# Custom_Board_1_Final.net
KiCad netlist of a schematic drawn in EAGLE
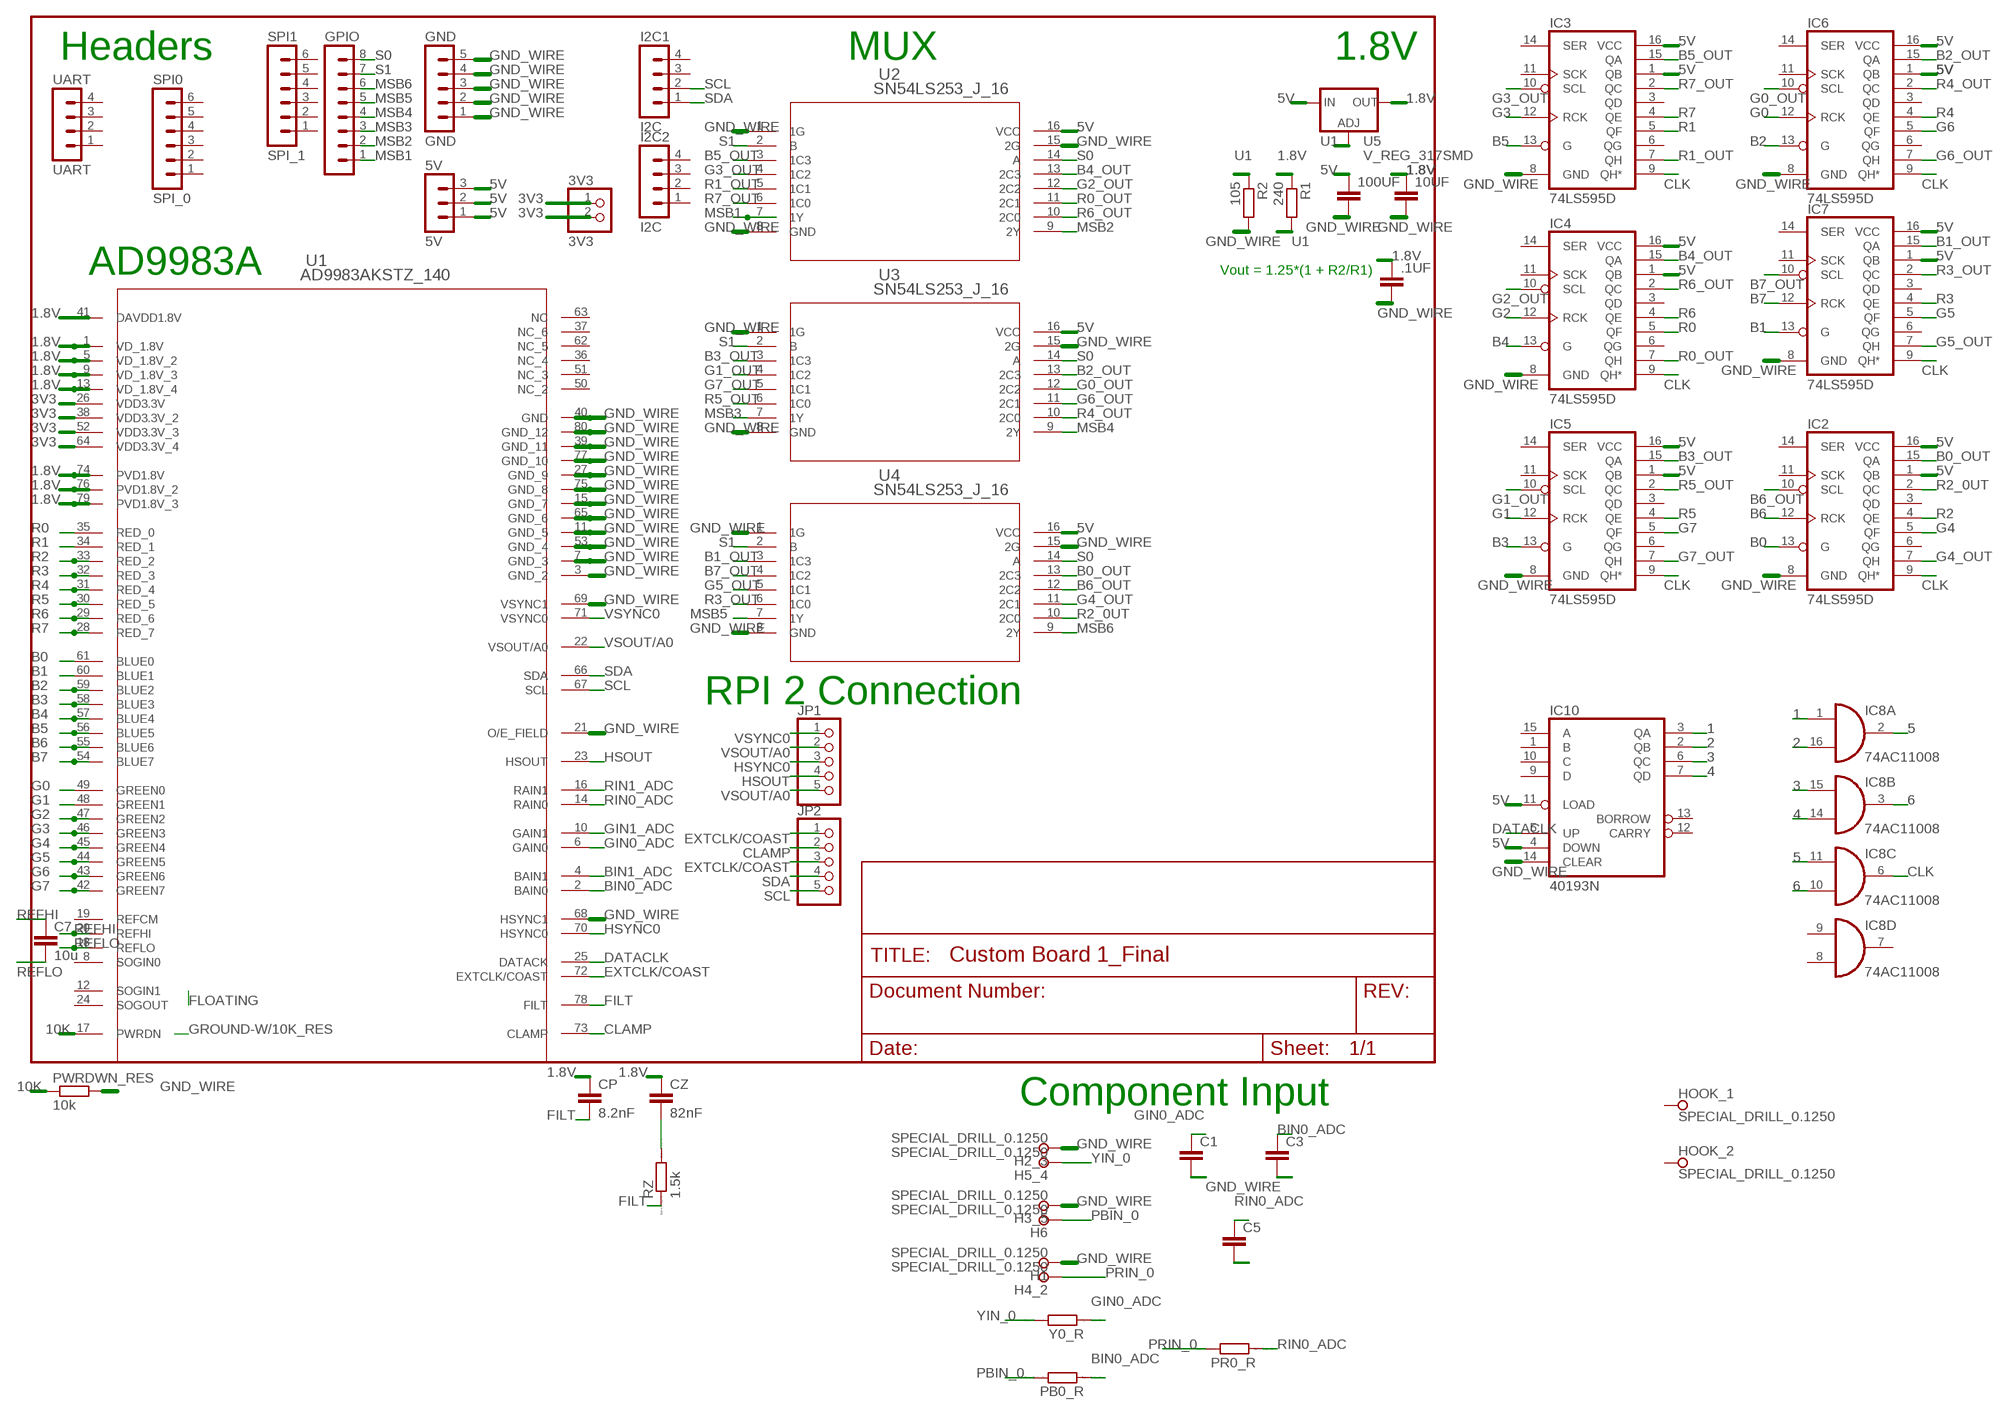
[diagram p0: schematic, sheet 1]

(export (version "E")
  (design (tool "Eeschema 10.0.6"))
  (components
    (comp (ref ".1UF")
      (value "C2.5/5")
      (footprint "eagle-import:C2.5-5")
      (libsource (lib "eagle-import") (part "C2.5/5"))
    )
    (comp (ref "3V3")
      (value "3V3")
      (footprint "eagle-import:1X02")
      (libsource (lib "eagle-import") (part "PINHD-1X2"))
    )
    (comp (ref "5V")
      (value "5V")
      (footprint "eagle-import:MA03-1")
      (libsource (lib "eagle-import") (part "MA03-1"))
    )
    (comp (ref "10UF")
      (value "C2.5/5")
      (footprint "eagle-import:C2.5-5")
      (libsource (lib "eagle-import") (part "C2.5/5"))
    )
    (comp (ref "100UF")
      (value "C2.5/5")
      (footprint "eagle-import:C2.5-5")
      (libsource (lib "eagle-import") (part "C2.5/5"))
    )
    (comp (ref "C1")
      (value "C2.5/5")
      (footprint "eagle-import:C2.5-5")
      (libsource (lib "eagle-import") (part "C2.5/5"))
    )
    (comp (ref "C3")
      (value "C2.5/5")
      (footprint "eagle-import:C2.5-5")
      (libsource (lib "eagle-import") (part "C2.5/5"))
    )
    (comp (ref "C5")
      (value "C2.5/5")
      (footprint "eagle-import:C2.5-5")
      (libsource (lib "eagle-import") (part "C2.5/5"))
    )
    (comp (ref "C7")
      (value "10u")
      (footprint "eagle-import:C2.5-5")
      (libsource (lib "eagle-import") (part "C2.5/5"))
    )
    (comp (ref "CP")
      (value "8.2nF")
      (footprint "eagle-import:C2.5-5")
      (libsource (lib "eagle-import") (part "C2.5/5"))
    )
    (comp (ref "CZ")
      (value "82nF")
      (footprint "eagle-import:C2.5-5")
      (libsource (lib "eagle-import") (part "C2.5/5"))
    )
    (comp (ref "GND")
      (value "GND")
      (footprint "eagle-import:MA05-1")
      (libsource (lib "eagle-import") (part "MA05-1"))
    )
    (comp (ref "GPIO")
      (value "MA08-1")
      (footprint "eagle-import:MA08-1")
      (libsource (lib "eagle-import") (part "MA08-1"))
    )
    (comp (ref "H1")
      (value "SPECIAL_DRILL_0.1250")
      (footprint "eagle-import:PAD_0.1250")
      (libsource (lib "eagle-import") (part "SPECIAL_DRILL_0.1250"))
    )
    (comp (ref "H2_3")
      (value "SPECIAL_DRILL_0.1250")
      (footprint "eagle-import:PAD_0.1250")
      (libsource (lib "eagle-import") (part "SPECIAL_DRILL_0.1250"))
    )
    (comp (ref "H3_5")
      (value "SPECIAL_DRILL_0.1250")
      (footprint "eagle-import:PAD_0.1250")
      (libsource (lib "eagle-import") (part "SPECIAL_DRILL_0.1250"))
    )
    (comp (ref "H4_2")
      (value "SPECIAL_DRILL_0.1250")
      (footprint "eagle-import:PAD_0.1250")
      (libsource (lib "eagle-import") (part "SPECIAL_DRILL_0.1250"))
    )
    (comp (ref "H5_4")
      (value "SPECIAL_DRILL_0.1250")
      (footprint "eagle-import:PAD_0.1250")
      (libsource (lib "eagle-import") (part "SPECIAL_DRILL_0.1250"))
    )
    (comp (ref "H6")
      (value "SPECIAL_DRILL_0.1250")
      (footprint "eagle-import:PAD_0.1250")
      (libsource (lib "eagle-import") (part "SPECIAL_DRILL_0.1250"))
    )
    (comp (ref "HOOK_1")
      (value "SPECIAL_DRILL_0.1250")
      (footprint "eagle-import:PAD_0.1250")
      (libsource (lib "eagle-import") (part "SPECIAL_DRILL_0.1250"))
    )
    (comp (ref "HOOK_2")
      (value "SPECIAL_DRILL_0.1250")
      (footprint "eagle-import:PAD_0.1250")
      (libsource (lib "eagle-import") (part "SPECIAL_DRILL_0.1250"))
    )
    (comp (ref "I2C1")
      (value "I2C")
      (footprint "eagle-import:MA04-1")
      (libsource (lib "eagle-import") (part "MA04-1"))
    )
    (comp (ref "I2C2")
      (value "I2C")
      (footprint "eagle-import:MA04-1")
      (libsource (lib "eagle-import") (part "MA04-1"))
    )
    (comp (ref "IC2")
      (value "74LS595D")
      (footprint "eagle-import:SO16")
      (libsource (lib "eagle-import") (part "74595DLS"))
    )
    (comp (ref "IC3")
      (value "74LS595D")
      (footprint "eagle-import:SO16")
      (libsource (lib "eagle-import") (part "74595DLS"))
    )
    (comp (ref "IC4")
      (value "74LS595D")
      (footprint "eagle-import:SO16")
      (libsource (lib "eagle-import") (part "74595DLS"))
    )
    (comp (ref "IC5")
      (value "74LS595D")
      (footprint "eagle-import:SO16")
      (libsource (lib "eagle-import") (part "74595DLS"))
    )
    (comp (ref "IC6")
      (value "74LS595D")
      (footprint "eagle-import:SO16")
      (libsource (lib "eagle-import") (part "74595DLS"))
    )
    (comp (ref "IC7")
      (value "74LS595D")
      (footprint "eagle-import:SO16")
      (libsource (lib "eagle-import") (part "74595DLS"))
    )
    (comp (ref "IC8")
      (value "74AC11008")
      (footprint "eagle-import:DIL16")
      (libsource (lib "eagle-import") (part "74AC11008"))
    )
    (comp (ref "IC10")
      (value "40193N")
      (footprint "eagle-import:DIL16")
      (libsource (lib "eagle-import") (part "40193N"))
    )
    (comp (ref "JP1")
      (value "PINHD-1X5")
      (footprint "eagle-import:1X05")
      (libsource (lib "eagle-import") (part "PINHD-1X5"))
    )
    (comp (ref "JP2")
      (value "PINHD-1X5")
      (footprint "eagle-import:1X05")
      (libsource (lib "eagle-import") (part "PINHD-1X5"))
    )
    (comp (ref "PB0_R")
      (value "R0204/7")
      (footprint "eagle-import:0204_7")
      (libsource (lib "eagle-import") (part "R0204/7"))
    )
    (comp (ref "PR0_R")
      (value "R0204/7")
      (footprint "eagle-import:0204_7")
      (libsource (lib "eagle-import") (part "R0204/7"))
    )
    (comp (ref "PWRDWN_RES")
      (value "10k")
      (footprint "eagle-import:0204_7")
      (libsource (lib "eagle-import") (part "R-EU_0204/7"))
    )
    (comp (ref "R1")
      (value "240")
      (footprint "eagle-import:0204_7")
      (libsource (lib "eagle-import") (part "R-EU_0204/7"))
    )
    (comp (ref "R2")
      (value "105")
      (footprint "eagle-import:0204_7")
      (libsource (lib "eagle-import") (part "R-EU_0204/7"))
    )
    (comp (ref "RZ")
      (value "1.5k")
      (footprint "eagle-import:0204_7")
      (libsource (lib "eagle-import") (part "R0204/7"))
    )
    (comp (ref "SPI0")
      (value "SPI_0")
      (footprint "eagle-import:MA06-1")
      (libsource (lib "eagle-import") (part "MA06-1"))
    )
    (comp (ref "SPI1")
      (value "SPI_1")
      (footprint "eagle-import:MA06-1")
      (libsource (lib "eagle-import") (part "MA06-1"))
    )
    (comp (ref "U1")
      (value "AD9983AKSTZ_140")
      (footprint "eagle-import:ST_80_2")
      (libsource (lib "eagle-import") (part "AD9983AKSTZ_140"))
    )
    (comp (ref "U2")
      (value "SN54LS253_J_16")
      (footprint "eagle-import:J16")
      (fields
        (field (name "GENERIC_PART_NUMBER") "SN54LS253")
        (field (name "MANUFACTURER") "Texas Instruments")
      )
      (libsource (lib "eagle-import") (part "SN54LS253_J_16"))
    )
    (comp (ref "U3")
      (value "SN54LS253_J_16")
      (footprint "eagle-import:J16")
      (fields
        (field (name "GENERIC_PART_NUMBER") "SN54LS253")
        (field (name "MANUFACTURER") "Texas Instruments")
      )
      (libsource (lib "eagle-import") (part "SN54LS253_J_16"))
    )
    (comp (ref "U4")
      (value "SN54LS253_J_16")
      (footprint "eagle-import:J16")
      (fields
        (field (name "GENERIC_PART_NUMBER") "SN54LS253")
        (field (name "MANUFACTURER") "Texas Instruments")
      )
      (libsource (lib "eagle-import") (part "SN54LS253_J_16"))
    )
    (comp (ref "U5")
      (value "V_REG_317SMD")
      (footprint "eagle-import:SOT223")
      (libsource (lib "eagle-import") (part "V_REG_317SMD"))
    )
    (comp (ref "UART")
      (value "UART")
      (footprint "eagle-import:MA04-1")
      (libsource (lib "eagle-import") (part "MA04-1"))
    )
    (comp (ref "Y0_R")
      (value "R0204/7")
      (footprint "eagle-import:0204_7")
      (libsource (lib "eagle-import") (part "R0204/7"))
    )
  )
  (nets
    (net (code "1") (name "/1") (class "Default")
      (node (ref "IC10") (pin "3") (pinfunction "QA_3") (pintype "output"))
      (node (ref "IC8") (pin "1") (pinfunction "I0_1") (pintype "input"))
    )
    (net (code "2") (name "/1.8V") (class "Default")
      (node (ref ".1UF") (pin "1") (pinfunction "1_1") (pintype "passive"))
      (node (ref "10UF") (pin "1") (pinfunction "1_1") (pintype "passive"))
      (node (ref "CP") (pin "1") (pinfunction "1_1") (pintype "passive"))
      (node (ref "CZ") (pin "1") (pinfunction "1_1") (pintype "passive"))
      (node (ref "R1") (pin "1") (pinfunction "1_1") (pintype "passive"))
      (node (ref "U1") (pin "1") (pinfunction "VD_1.8V_1") (pintype "passive"))
      (node (ref "U1") (pin "13") (pinfunction "VD_1.8V_4_13") (pintype "passive"))
      (node (ref "U1") (pin "41") (pinfunction "DAVDD1.8V_41") (pintype "passive"))
      (node (ref "U1") (pin "5") (pinfunction "VD_1.8V_2_5") (pintype "passive"))
      (node (ref "U1") (pin "74") (pinfunction "PVD1.8V_74") (pintype "passive"))
      (node (ref "U1") (pin "76") (pinfunction "PVD1.8V_2_76") (pintype "passive"))
      (node (ref "U1") (pin "79") (pinfunction "PVD1.8V_3_79") (pintype "passive"))
      (node (ref "U1") (pin "9") (pinfunction "VD_1.8V_3_9") (pintype "passive"))
      (node (ref "U5") (pin "2") (pinfunction "OUT_2") (pintype "output"))
    )
    (net (code "3") (name "/2") (class "Default")
      (node (ref "IC10") (pin "2") (pinfunction "QB_2") (pintype "output"))
      (node (ref "IC8") (pin "16") (pinfunction "I1_16") (pintype "input"))
    )
    (net (code "4") (name "/3") (class "Default")
      (node (ref "IC10") (pin "6") (pinfunction "QC_6") (pintype "output"))
      (node (ref "IC8") (pin "15") (pinfunction "I0_15") (pintype "input"))
    )
    (net (code "5") (name "/3V3") (class "Default")
      (node (ref "3V3") (pin "1") (pinfunction "1_1") (pintype "passive"))
      (node (ref "3V3") (pin "2") (pinfunction "2_2") (pintype "passive"))
      (node (ref "U1") (pin "26") (pinfunction "VDD3.3V_26") (pintype "passive"))
      (node (ref "U1") (pin "38") (pinfunction "VDD3.3V_2_38") (pintype "passive"))
      (node (ref "U1") (pin "52") (pinfunction "VDD3.3V_3_52") (pintype "passive"))
      (node (ref "U1") (pin "64") (pinfunction "VDD3.3V_4_64") (pintype "passive"))
    )
    (net (code "6") (name "/4") (class "Default")
      (node (ref "IC10") (pin "7") (pinfunction "QD_7") (pintype "output"))
      (node (ref "IC8") (pin "14") (pinfunction "I1_14") (pintype "input"))
    )
    (net (code "7") (name "/5") (class "Default")
      (node (ref "IC8") (pin "11") (pinfunction "I0_11") (pintype "input"))
      (node (ref "IC8") (pin "2") (pinfunction "O_2") (pintype "output"))
    )
    (net (code "8") (name "/5V") (class "Default")
      (node (ref "100UF") (pin "1") (pinfunction "1_1") (pintype "passive"))
      (node (ref "5V") (pin "1") (pinfunction "1_1") (pintype "passive"))
      (node (ref "5V") (pin "2") (pinfunction "2_2") (pintype "passive"))
      (node (ref "5V") (pin "3") (pinfunction "3_3") (pintype "passive"))
      (node (ref "IC10") (pin "11") (pinfunction "LOAD_11") (pintype "input"))
      (node (ref "IC10") (pin "4") (pinfunction "DOWN_4") (pintype "input"))
      (node (ref "IC2") (pin "1") (pinfunction "QB_1") (pintype "tri_state"))
      (node (ref "IC2") (pin "16") (pinfunction "VCC_16") (pintype "power_in"))
      (node (ref "IC3") (pin "1") (pinfunction "QB_1") (pintype "tri_state"))
      (node (ref "IC3") (pin "16") (pinfunction "VCC_16") (pintype "power_in"))
      (node (ref "IC4") (pin "1") (pinfunction "QB_1") (pintype "tri_state"))
      (node (ref "IC4") (pin "16") (pinfunction "VCC_16") (pintype "power_in"))
      (node (ref "IC5") (pin "1") (pinfunction "QB_1") (pintype "tri_state"))
      (node (ref "IC5") (pin "16") (pinfunction "VCC_16") (pintype "power_in"))
      (node (ref "IC6") (pin "1") (pinfunction "QB_1") (pintype "tri_state"))
      (node (ref "IC6") (pin "16") (pinfunction "VCC_16") (pintype "power_in"))
      (node (ref "IC7") (pin "1") (pinfunction "QB_1") (pintype "tri_state"))
      (node (ref "IC7") (pin "16") (pinfunction "VCC_16") (pintype "power_in"))
      (node (ref "U2") (pin "16") (pinfunction "VCC_16") (pintype "power_in"))
      (node (ref "U3") (pin "16") (pinfunction "VCC_16") (pintype "power_in"))
      (node (ref "U4") (pin "16") (pinfunction "VCC_16") (pintype "power_in"))
      (node (ref "U5") (pin "3") (pinfunction "IN_3") (pintype "input"))
    )
    (net (code "9") (name "/6") (class "Default")
      (node (ref "IC8") (pin "10") (pinfunction "I1_10") (pintype "input"))
      (node (ref "IC8") (pin "3") (pinfunction "O_3") (pintype "output"))
    )
    (net (code "10") (name "/10K") (class "Default")
      (node (ref "PWRDWN_RES") (pin "1") (pinfunction "1_1") (pintype "passive"))
      (node (ref "U1") (pin "17") (pinfunction "PWRDN_17") (pintype "passive"))
    )
    (net (code "11") (name "/B0") (class "Default")
      (node (ref "IC2") (pin "13") (pinfunction "G_13") (pintype "input"))
      (node (ref "U1") (pin "61") (pinfunction "BLUE0_61") (pintype "passive"))
    )
    (net (code "12") (name "/B0_OUT") (class "Default")
      (node (ref "IC2") (pin "15") (pinfunction "QA_15") (pintype "tri_state"))
      (node (ref "U4") (pin "13") (pinfunction "2C3_13") (pintype "input"))
    )
    (net (code "13") (name "/B1") (class "Default")
      (node (ref "IC7") (pin "13") (pinfunction "G_13") (pintype "input"))
      (node (ref "U1") (pin "60") (pinfunction "BLUE1_60") (pintype "passive"))
    )
    (net (code "14") (name "/B1_OUT") (class "Default")
      (node (ref "IC7") (pin "15") (pinfunction "QA_15") (pintype "tri_state"))
      (node (ref "U4") (pin "3") (pinfunction "1C3_3") (pintype "input"))
    )
    (net (code "15") (name "/B2") (class "Default")
      (node (ref "IC6") (pin "13") (pinfunction "G_13") (pintype "input"))
      (node (ref "U1") (pin "59") (pinfunction "BLUE2_59") (pintype "passive"))
    )
    (net (code "16") (name "/B2_OUT") (class "Default")
      (node (ref "IC6") (pin "15") (pinfunction "QA_15") (pintype "tri_state"))
      (node (ref "U3") (pin "13") (pinfunction "2C3_13") (pintype "input"))
    )
    (net (code "17") (name "/B3") (class "Default")
      (node (ref "IC5") (pin "13") (pinfunction "G_13") (pintype "input"))
      (node (ref "U1") (pin "58") (pinfunction "BLUE3_58") (pintype "passive"))
    )
    (net (code "18") (name "/B3_OUT") (class "Default")
      (node (ref "IC5") (pin "15") (pinfunction "QA_15") (pintype "tri_state"))
      (node (ref "U3") (pin "3") (pinfunction "1C3_3") (pintype "input"))
    )
    (net (code "19") (name "/B4") (class "Default")
      (node (ref "IC4") (pin "13") (pinfunction "G_13") (pintype "input"))
      (node (ref "U1") (pin "57") (pinfunction "BLUE4_57") (pintype "passive"))
    )
    (net (code "20") (name "/B4_OUT") (class "Default")
      (node (ref "IC4") (pin "15") (pinfunction "QA_15") (pintype "tri_state"))
      (node (ref "U2") (pin "13") (pinfunction "2C3_13") (pintype "input"))
    )
    (net (code "21") (name "/B5") (class "Default")
      (node (ref "IC3") (pin "13") (pinfunction "G_13") (pintype "input"))
      (node (ref "U1") (pin "56") (pinfunction "BLUE5_56") (pintype "passive"))
    )
    (net (code "22") (name "/B5_OUT") (class "Default")
      (node (ref "IC3") (pin "15") (pinfunction "QA_15") (pintype "tri_state"))
      (node (ref "U2") (pin "3") (pinfunction "1C3_3") (pintype "input"))
    )
    (net (code "23") (name "/B6") (class "Default")
      (node (ref "IC2") (pin "12") (pinfunction "RCK_12") (pintype "input"))
      (node (ref "U1") (pin "55") (pinfunction "BLUE6_55") (pintype "passive"))
    )
    (net (code "24") (name "/B6_OUT") (class "Default")
      (node (ref "IC2") (pin "10") (pinfunction "SCL_10") (pintype "input"))
      (node (ref "U4") (pin "12") (pinfunction "2C2_12") (pintype "input"))
    )
    (net (code "25") (name "/B7") (class "Default")
      (node (ref "IC7") (pin "12") (pinfunction "RCK_12") (pintype "input"))
      (node (ref "U1") (pin "54") (pinfunction "BLUE7_54") (pintype "passive"))
    )
    (net (code "26") (name "/B7_OUT") (class "Default")
      (node (ref "IC7") (pin "10") (pinfunction "SCL_10") (pintype "input"))
      (node (ref "U4") (pin "4") (pinfunction "1C2_4") (pintype "input"))
    )
    (net (code "27") (name "/BIN0_ADC") (class "Default")
      (node (ref "C3") (pin "1") (pinfunction "1_1") (pintype "passive"))
      (node (ref "PB0_R") (pin "1") (pinfunction "1_1") (pintype "passive"))
      (node (ref "U1") (pin "2") (pinfunction "BAIN0_2") (pintype "passive"))
    )
    (net (code "28") (name "/BIN1_ADC") (class "Default")
      (node (ref "U1") (pin "4") (pinfunction "BAIN1_4") (pintype "passive"))
    )
    (net (code "29") (name "/CLAMP") (class "Default")
      (node (ref "JP2") (pin "2") (pinfunction "2_2") (pintype "passive"))
      (node (ref "U1") (pin "73") (pinfunction "CLAMP_73") (pintype "passive"))
    )
    (net (code "30") (name "/CLK") (class "Default")
      (node (ref "IC2") (pin "9") (pinfunction "QH*_9") (pintype "tri_state"))
      (node (ref "IC3") (pin "9") (pinfunction "QH*_9") (pintype "tri_state"))
      (node (ref "IC4") (pin "9") (pinfunction "QH*_9") (pintype "tri_state"))
      (node (ref "IC5") (pin "9") (pinfunction "QH*_9") (pintype "tri_state"))
      (node (ref "IC6") (pin "9") (pinfunction "QH*_9") (pintype "tri_state"))
      (node (ref "IC7") (pin "9") (pinfunction "QH*_9") (pintype "tri_state"))
      (node (ref "IC8") (pin "6") (pinfunction "O_6") (pintype "output"))
    )
    (net (code "31") (name "/DATACLK") (class "Default")
      (node (ref "IC10") (pin "5") (pinfunction "UP_5") (pintype "input"))
      (node (ref "U1") (pin "25") (pinfunction "DATACK_25") (pintype "passive"))
    )
    (net (code "32") (name "/EXTCLK{slash}COAST") (class "Default")
      (node (ref "JP2") (pin "1") (pinfunction "1_1") (pintype "passive"))
      (node (ref "JP2") (pin "3") (pinfunction "3_3") (pintype "passive"))
      (node (ref "U1") (pin "72") (pinfunction "EXTCLK/COAST_72") (pintype "passive"))
    )
    (net (code "33") (name "/FILT") (class "Default")
      (node (ref "CP") (pin "2") (pinfunction "2_2") (pintype "passive"))
      (node (ref "RZ") (pin "1") (pinfunction "1_1") (pintype "passive"))
      (node (ref "U1") (pin "78") (pinfunction "FILT_78") (pintype "passive"))
    )
    (net (code "35") (name "/G0") (class "Default")
      (node (ref "IC6") (pin "12") (pinfunction "RCK_12") (pintype "input"))
      (node (ref "U1") (pin "49") (pinfunction "GREEN0_49") (pintype "passive"))
    )
    (net (code "36") (name "/G0_OUT") (class "Default")
      (node (ref "IC6") (pin "10") (pinfunction "SCL_10") (pintype "input"))
      (node (ref "U3") (pin "12") (pinfunction "2C2_12") (pintype "input"))
    )
    (net (code "37") (name "/G1") (class "Default")
      (node (ref "IC5") (pin "12") (pinfunction "RCK_12") (pintype "input"))
      (node (ref "U1") (pin "48") (pinfunction "GREEN1_48") (pintype "passive"))
    )
    (net (code "38") (name "/G1_OUT") (class "Default")
      (node (ref "IC5") (pin "10") (pinfunction "SCL_10") (pintype "input"))
      (node (ref "U3") (pin "4") (pinfunction "1C2_4") (pintype "input"))
    )
    (net (code "39") (name "/G2") (class "Default")
      (node (ref "IC4") (pin "12") (pinfunction "RCK_12") (pintype "input"))
      (node (ref "U1") (pin "47") (pinfunction "GREEN2_47") (pintype "passive"))
    )
    (net (code "40") (name "/G2_OUT") (class "Default")
      (node (ref "IC4") (pin "10") (pinfunction "SCL_10") (pintype "input"))
      (node (ref "U2") (pin "12") (pinfunction "2C2_12") (pintype "input"))
    )
    (net (code "41") (name "/G3") (class "Default")
      (node (ref "IC3") (pin "12") (pinfunction "RCK_12") (pintype "input"))
      (node (ref "U1") (pin "46") (pinfunction "GREEN3_46") (pintype "passive"))
    )
    (net (code "42") (name "/G3_OUT") (class "Default")
      (node (ref "IC3") (pin "10") (pinfunction "SCL_10") (pintype "input"))
      (node (ref "U2") (pin "4") (pinfunction "1C2_4") (pintype "input"))
    )
    (net (code "43") (name "/G4") (class "Default")
      (node (ref "IC2") (pin "5") (pinfunction "QF_5") (pintype "tri_state"))
      (node (ref "U1") (pin "45") (pinfunction "GREEN4_45") (pintype "passive"))
    )
    (net (code "44") (name "/G4_OUT") (class "Default")
      (node (ref "IC2") (pin "7") (pinfunction "QH_7") (pintype "tri_state"))
      (node (ref "U4") (pin "11") (pinfunction "2C1_11") (pintype "input"))
    )
    (net (code "45") (name "/G5") (class "Default")
      (node (ref "IC7") (pin "5") (pinfunction "QF_5") (pintype "tri_state"))
      (node (ref "U1") (pin "44") (pinfunction "GREEN5_44") (pintype "passive"))
    )
    (net (code "46") (name "/G5_OUT") (class "Default")
      (node (ref "IC7") (pin "7") (pinfunction "QH_7") (pintype "tri_state"))
      (node (ref "U4") (pin "5") (pinfunction "1C1_5") (pintype "input"))
    )
    (net (code "47") (name "/G6") (class "Default")
      (node (ref "IC6") (pin "5") (pinfunction "QF_5") (pintype "tri_state"))
      (node (ref "U1") (pin "43") (pinfunction "GREEN6_43") (pintype "passive"))
    )
    (net (code "48") (name "/G6_OUT") (class "Default")
      (node (ref "IC6") (pin "7") (pinfunction "QH_7") (pintype "tri_state"))
      (node (ref "U3") (pin "11") (pinfunction "2C1_11") (pintype "input"))
    )
    (net (code "49") (name "/G7") (class "Default")
      (node (ref "IC5") (pin "5") (pinfunction "QF_5") (pintype "tri_state"))
      (node (ref "U1") (pin "42") (pinfunction "GREEN7_42") (pintype "passive"))
    )
    (net (code "50") (name "/G7_OUT") (class "Default")
      (node (ref "IC5") (pin "7") (pinfunction "QH_7") (pintype "tri_state"))
      (node (ref "U3") (pin "5") (pinfunction "1C1_5") (pintype "input"))
    )
    (net (code "51") (name "/GIN0_ADC") (class "Default")
      (node (ref "C1") (pin "1") (pinfunction "1_1") (pintype "passive"))
      (node (ref "U1") (pin "6") (pinfunction "GAIN0_6") (pintype "passive"))
      (node (ref "Y0_R") (pin "1") (pinfunction "1_1") (pintype "passive"))
    )
    (net (code "52") (name "/GIN1_ADC") (class "Default")
      (node (ref "U1") (pin "10") (pinfunction "GAIN1_10") (pintype "passive"))
    )
    (net (code "53") (name "/GND_WIRE") (class "Default")
      (node (ref ".1UF") (pin "2") (pinfunction "2_2") (pintype "passive"))
      (node (ref "100UF") (pin "2") (pinfunction "2_2") (pintype "passive"))
      (node (ref "10UF") (pin "2") (pinfunction "2_2") (pintype "passive"))
      (node (ref "C1") (pin "2") (pinfunction "2_2") (pintype "passive"))
      (node (ref "C3") (pin "2") (pinfunction "2_2") (pintype "passive"))
      (node (ref "C5") (pin "2") (pinfunction "2_2") (pintype "passive"))
      (node (ref "GND") (pin "1") (pinfunction "1_1") (pintype "passive"))
      (node (ref "GND") (pin "2") (pinfunction "2_2") (pintype "passive"))
      (node (ref "GND") (pin "3") (pinfunction "3_3") (pintype "passive"))
      (node (ref "GND") (pin "4") (pinfunction "4_4") (pintype "passive"))
      (node (ref "GND") (pin "5") (pinfunction "5_5") (pintype "passive"))
      (node (ref "H1") (pin "1") (pinfunction "1_1") (pintype "passive"))
      (node (ref "H2_3") (pin "1") (pinfunction "1_1") (pintype "passive"))
      (node (ref "H3_5") (pin "1") (pinfunction "1_1") (pintype "passive"))
      (node (ref "IC10") (pin "14") (pinfunction "CLEAR_14") (pintype "input"))
      (node (ref "IC2") (pin "8") (pinfunction "GND_8") (pintype "power_in"))
      (node (ref "IC3") (pin "8") (pinfunction "GND_8") (pintype "power_in"))
      (node (ref "IC4") (pin "8") (pinfunction "GND_8") (pintype "power_in"))
      (node (ref "IC5") (pin "8") (pinfunction "GND_8") (pintype "power_in"))
      (node (ref "IC6") (pin "8") (pinfunction "GND_8") (pintype "power_in"))
      (node (ref "IC7") (pin "8") (pinfunction "GND_8") (pintype "power_in"))
      (node (ref "PWRDWN_RES") (pin "2") (pinfunction "2_2") (pintype "passive"))
      (node (ref "R2") (pin "2") (pinfunction "2_2") (pintype "passive"))
      (node (ref "U1") (pin "11") (pinfunction "GND_5_11") (pintype "passive"))
      (node (ref "U1") (pin "15") (pinfunction "GND_7_15") (pintype "passive"))
      (node (ref "U1") (pin "21") (pinfunction "O/E_FIELD_21") (pintype "passive"))
      (node (ref "U1") (pin "27") (pinfunction "GND_9_27") (pintype "passive"))
      (node (ref "U1") (pin "3") (pinfunction "GND_2_3") (pintype "passive"))
      (node (ref "U1") (pin "39") (pinfunction "GND_11_39") (pintype "passive"))
      (node (ref "U1") (pin "40") (pinfunction "GND_40") (pintype "passive"))
      (node (ref "U1") (pin "53") (pinfunction "GND_4_53") (pintype "passive"))
      (node (ref "U1") (pin "65") (pinfunction "GND_6_65") (pintype "passive"))
      (node (ref "U1") (pin "68") (pinfunction "HSYNC1_68") (pintype "passive"))
      (node (ref "U1") (pin "69") (pinfunction "VSYNC1_69") (pintype "passive"))
      (node (ref "U1") (pin "7") (pinfunction "GND_3_7") (pintype "passive"))
      (node (ref "U1") (pin "75") (pinfunction "GND_8_75") (pintype "passive"))
      (node (ref "U1") (pin "77") (pinfunction "GND_10_77") (pintype "passive"))
      (node (ref "U1") (pin "80") (pinfunction "GND_12_80") (pintype "passive"))
      (node (ref "U2") (pin "1") (pinfunction "1G_1") (pintype "input"))
      (node (ref "U2") (pin "15") (pinfunction "2G_15") (pintype "input"))
      (node (ref "U2") (pin "8") (pinfunction "GND_8") (pintype "power_in"))
      (node (ref "U3") (pin "1") (pinfunction "1G_1") (pintype "input"))
      (node (ref "U3") (pin "15") (pinfunction "2G_15") (pintype "input"))
      (node (ref "U3") (pin "8") (pinfunction "GND_8") (pintype "power_in"))
      (node (ref "U4") (pin "1") (pinfunction "1G_1") (pintype "input"))
      (node (ref "U4") (pin "15") (pinfunction "2G_15") (pintype "input"))
      (node (ref "U4") (pin "8") (pinfunction "GND_8") (pintype "power_in"))
    )
    (net (code "55") (name "/HSOUT") (class "Default")
      (node (ref "JP1") (pin "4") (pinfunction "4_4") (pintype "passive"))
      (node (ref "U1") (pin "23") (pinfunction "HSOUT_23") (pintype "passive"))
    )
    (net (code "56") (name "/HSYNC0") (class "Default")
      (node (ref "JP1") (pin "3") (pinfunction "3_3") (pintype "passive"))
      (node (ref "U1") (pin "70") (pinfunction "HSYNC0_70") (pintype "passive"))
    )
    (net (code "57") (name "/MSB1") (class "Default")
      (node (ref "GPIO") (pin "1") (pinfunction "1_1") (pintype "passive"))
      (node (ref "U2") (pin "7") (pinfunction "1Y_7") (pintype "output"))
    )
    (net (code "58") (name "/MSB2") (class "Default")
      (node (ref "GPIO") (pin "2") (pinfunction "2_2") (pintype "passive"))
      (node (ref "U2") (pin "9") (pinfunction "2Y_9") (pintype "output"))
    )
    (net (code "59") (name "/MSB3") (class "Default")
      (node (ref "GPIO") (pin "3") (pinfunction "3_3") (pintype "passive"))
      (node (ref "U3") (pin "7") (pinfunction "1Y_7") (pintype "output"))
    )
    (net (code "60") (name "/MSB4") (class "Default")
      (node (ref "GPIO") (pin "4") (pinfunction "4_4") (pintype "passive"))
      (node (ref "U3") (pin "9") (pinfunction "2Y_9") (pintype "output"))
    )
    (net (code "61") (name "/MSB5") (class "Default")
      (node (ref "GPIO") (pin "5") (pinfunction "5_5") (pintype "passive"))
      (node (ref "U4") (pin "7") (pinfunction "1Y_7") (pintype "output"))
    )
    (net (code "62") (name "/MSB6") (class "Default")
      (node (ref "GPIO") (pin "6") (pinfunction "6_6") (pintype "passive"))
      (node (ref "U4") (pin "9") (pinfunction "2Y_9") (pintype "output"))
    )
    (net (code "63") (name "/PBIN_0") (class "Default")
      (node (ref "H6") (pin "1") (pinfunction "1_1") (pintype "passive"))
      (node (ref "PB0_R") (pin "2") (pinfunction "2_2") (pintype "passive"))
    )
    (net (code "64") (name "/PRIN_0") (class "Default")
      (node (ref "H4_2") (pin "1") (pinfunction "1_1") (pintype "passive"))
      (node (ref "PR0_R") (pin "2") (pinfunction "2_2") (pintype "passive"))
    )
    (net (code "65") (name "/R0") (class "Default")
      (node (ref "IC4") (pin "5") (pinfunction "QF_5") (pintype "tri_state"))
      (node (ref "U1") (pin "35") (pinfunction "RED_0_35") (pintype "passive"))
    )
    (net (code "66") (name "/R0_OUT") (class "Default")
      (node (ref "IC4") (pin "7") (pinfunction "QH_7") (pintype "tri_state"))
      (node (ref "U2") (pin "11") (pinfunction "2C1_11") (pintype "input"))
    )
    (net (code "67") (name "/R1") (class "Default")
      (node (ref "IC3") (pin "5") (pinfunction "QF_5") (pintype "tri_state"))
      (node (ref "U1") (pin "34") (pinfunction "RED_1_34") (pintype "passive"))
    )
    (net (code "68") (name "/R1_OUT") (class "Default")
      (node (ref "IC3") (pin "7") (pinfunction "QH_7") (pintype "tri_state"))
      (node (ref "U2") (pin "5") (pinfunction "1C1_5") (pintype "input"))
    )
    (net (code "69") (name "/R2") (class "Default")
      (node (ref "IC2") (pin "4") (pinfunction "QE_4") (pintype "tri_state"))
      (node (ref "U1") (pin "33") (pinfunction "RED_2_33") (pintype "passive"))
    )
    (net (code "70") (name "/R2_0UT") (class "Default")
      (node (ref "IC2") (pin "2") (pinfunction "QC_2") (pintype "tri_state"))
      (node (ref "U4") (pin "10") (pinfunction "2C0_10") (pintype "input"))
    )
    (net (code "71") (name "/R3") (class "Default")
      (node (ref "IC7") (pin "4") (pinfunction "QE_4") (pintype "tri_state"))
      (node (ref "U1") (pin "32") (pinfunction "RED_3_32") (pintype "passive"))
    )
    (net (code "72") (name "/R3_OUT") (class "Default")
      (node (ref "IC7") (pin "2") (pinfunction "QC_2") (pintype "tri_state"))
      (node (ref "U4") (pin "6") (pinfunction "1C0_6") (pintype "input"))
    )
    (net (code "73") (name "/R4") (class "Default")
      (node (ref "IC6") (pin "4") (pinfunction "QE_4") (pintype "tri_state"))
      (node (ref "U1") (pin "31") (pinfunction "RED_4_31") (pintype "passive"))
    )
    (net (code "74") (name "/R4_OUT") (class "Default")
      (node (ref "IC6") (pin "2") (pinfunction "QC_2") (pintype "tri_state"))
      (node (ref "U3") (pin "10") (pinfunction "2C0_10") (pintype "input"))
    )
    (net (code "75") (name "/R5") (class "Default")
      (node (ref "IC5") (pin "4") (pinfunction "QE_4") (pintype "tri_state"))
      (node (ref "U1") (pin "30") (pinfunction "RED_5_30") (pintype "passive"))
    )
    (net (code "76") (name "/R5_OUT") (class "Default")
      (node (ref "IC5") (pin "2") (pinfunction "QC_2") (pintype "tri_state"))
      (node (ref "U3") (pin "6") (pinfunction "1C0_6") (pintype "input"))
    )
    (net (code "77") (name "/R6") (class "Default")
      (node (ref "IC4") (pin "4") (pinfunction "QE_4") (pintype "tri_state"))
      (node (ref "U1") (pin "29") (pinfunction "RED_6_29") (pintype "passive"))
    )
    (net (code "78") (name "/R6_OUT") (class "Default")
      (node (ref "IC4") (pin "2") (pinfunction "QC_2") (pintype "tri_state"))
      (node (ref "U2") (pin "10") (pinfunction "2C0_10") (pintype "input"))
    )
    (net (code "79") (name "/R7") (class "Default")
      (node (ref "IC3") (pin "4") (pinfunction "QE_4") (pintype "tri_state"))
      (node (ref "U1") (pin "28") (pinfunction "RED_7_28") (pintype "passive"))
    )
    (net (code "80") (name "/R7_OUT") (class "Default")
      (node (ref "IC3") (pin "2") (pinfunction "QC_2") (pintype "tri_state"))
      (node (ref "U2") (pin "6") (pinfunction "1C0_6") (pintype "input"))
    )
    (net (code "81") (name "/REFHI") (class "Default")
      (node (ref "C7") (pin "1") (pinfunction "1_1") (pintype "passive"))
      (node (ref "U1") (pin "20") (pinfunction "REFHI_20") (pintype "passive"))
    )
    (net (code "82") (name "/REFLO") (class "Default")
      (node (ref "C7") (pin "2") (pinfunction "2_2") (pintype "passive"))
      (node (ref "U1") (pin "18") (pinfunction "REFLO_18") (pintype "passive"))
    )
    (net (code "83") (name "/RIN0_ADC") (class "Default")
      (node (ref "C5") (pin "1") (pinfunction "1_1") (pintype "passive"))
      (node (ref "PR0_R") (pin "1") (pinfunction "1_1") (pintype "passive"))
      (node (ref "U1") (pin "14") (pinfunction "RAIN0_14") (pintype "passive"))
    )
    (net (code "84") (name "/RIN1_ADC") (class "Default")
      (node (ref "U1") (pin "16") (pinfunction "RAIN1_16") (pintype "passive"))
    )
    (net (code "85") (name "/S0") (class "Default")
      (node (ref "GPIO") (pin "8") (pinfunction "8_8") (pintype "passive"))
      (node (ref "U2") (pin "14") (pinfunction "A_14") (pintype "input"))
      (node (ref "U3") (pin "14") (pinfunction "A_14") (pintype "input"))
      (node (ref "U4") (pin "14") (pinfunction "A_14") (pintype "input"))
    )
    (net (code "86") (name "/S1") (class "Default")
      (node (ref "GPIO") (pin "7") (pinfunction "7_7") (pintype "passive"))
      (node (ref "U2") (pin "2") (pinfunction "B_2") (pintype "input"))
      (node (ref "U3") (pin "2") (pinfunction "B_2") (pintype "input"))
      (node (ref "U4") (pin "2") (pinfunction "B_2") (pintype "input"))
    )
    (net (code "87") (name "/SCL") (class "Default")
      (node (ref "I2C1") (pin "2") (pinfunction "2_2") (pintype "passive"))
      (node (ref "JP2") (pin "5") (pinfunction "5_5") (pintype "passive"))
      (node (ref "U1") (pin "67") (pinfunction "SCL_67") (pintype "passive"))
    )
    (net (code "88") (name "/SDA") (class "Default")
      (node (ref "I2C1") (pin "1") (pinfunction "1_1") (pintype "passive"))
      (node (ref "JP2") (pin "4") (pinfunction "4_4") (pintype "passive"))
      (node (ref "U1") (pin "66") (pinfunction "SDA_66") (pintype "passive"))
    )
    (net (code "89") (name "/U1") (class "Default")
      (node (ref "R1") (pin "2") (pinfunction "2_2") (pintype "passive"))
      (node (ref "R2") (pin "1") (pinfunction "1_1") (pintype "passive"))
      (node (ref "U5") (pin "1") (pinfunction "ADJ_1") (pintype "input"))
    )
    (net (code "90") (name "/VSOUT{slash}A0") (class "Default")
      (node (ref "JP1") (pin "2") (pinfunction "2_2") (pintype "passive"))
      (node (ref "JP1") (pin "5") (pinfunction "5_5") (pintype "passive"))
      (node (ref "U1") (pin "22") (pinfunction "VSOUT/A0_22") (pintype "passive"))
    )
    (net (code "91") (name "/VSYNC0") (class "Default")
      (node (ref "JP1") (pin "1") (pinfunction "1_1") (pintype "passive"))
      (node (ref "U1") (pin "71") (pinfunction "VSYNC0_71") (pintype "passive"))
    )
    (net (code "92") (name "/YIN_0") (class "Default")
      (node (ref "H5_4") (pin "1") (pinfunction "1_1") (pintype "passive"))
      (node (ref "Y0_R") (pin "2") (pinfunction "2_2") (pintype "passive"))
    )
    (net (code "93") (name "Net-(CZ-Pad2)") (class "Default")
      (node (ref "CZ") (pin "2") (pinfunction "2_2") (pintype "passive"))
      (node (ref "RZ") (pin "2") (pinfunction "2_2") (pintype "passive"))
    )
    (net (code "94") (name "unconnected-(HOOK_1-Pad1)") (class "Default")
      (node (ref "HOOK_1") (pin "1") (pinfunction "1_1") (pintype "passive"))
    )
    (net (code "95") (name "unconnected-(HOOK_2-Pad1)") (class "Default")
      (node (ref "HOOK_2") (pin "1") (pinfunction "1_1") (pintype "passive"))
    )
    (net (code "96") (name "unconnected-(I2C1-Pad3)") (class "Default")
      (node (ref "I2C1") (pin "3") (pinfunction "3_3") (pintype "passive"))
    )
    (net (code "97") (name "unconnected-(I2C1-Pad4)") (class "Default")
      (node (ref "I2C1") (pin "4") (pinfunction "4_4") (pintype "passive"))
    )
    (net (code "98") (name "unconnected-(I2C2-Pad1)") (class "Default")
      (node (ref "I2C2") (pin "1") (pinfunction "1_1") (pintype "passive"))
    )
    (net (code "99") (name "unconnected-(I2C2-Pad2)") (class "Default")
      (node (ref "I2C2") (pin "2") (pinfunction "2_2") (pintype "passive"))
    )
    (net (code "100") (name "unconnected-(I2C2-Pad3)") (class "Default")
      (node (ref "I2C2") (pin "3") (pinfunction "3_3") (pintype "passive"))
    )
    (net (code "101") (name "unconnected-(I2C2-Pad4)") (class "Default")
      (node (ref "I2C2") (pin "4") (pinfunction "4_4") (pintype "passive"))
    )
    (net (code "102") (name "unconnected-(IC2-QD-Pad3)") (class "Default")
      (node (ref "IC2") (pin "3") (pinfunction "QD_3") (pintype "tri_state"))
    )
    (net (code "103") (name "unconnected-(IC2-QG-Pad6)") (class "Default")
      (node (ref "IC2") (pin "6") (pinfunction "QG_6") (pintype "tri_state"))
    )
    (net (code "104") (name "unconnected-(IC2-SCK-Pad11)") (class "Default")
      (node (ref "IC2") (pin "11") (pinfunction "SCK_11") (pintype "input"))
    )
    (net (code "105") (name "unconnected-(IC2-SER-Pad14)") (class "Default")
      (node (ref "IC2") (pin "14") (pinfunction "SER_14") (pintype "input"))
    )
    (net (code "106") (name "unconnected-(IC3-QD-Pad3)") (class "Default")
      (node (ref "IC3") (pin "3") (pinfunction "QD_3") (pintype "tri_state"))
    )
    (net (code "107") (name "unconnected-(IC3-QG-Pad6)") (class "Default")
      (node (ref "IC3") (pin "6") (pinfunction "QG_6") (pintype "tri_state"))
    )
    (net (code "108") (name "unconnected-(IC3-SCK-Pad11)") (class "Default")
      (node (ref "IC3") (pin "11") (pinfunction "SCK_11") (pintype "input"))
    )
    (net (code "109") (name "unconnected-(IC3-SER-Pad14)") (class "Default")
      (node (ref "IC3") (pin "14") (pinfunction "SER_14") (pintype "input"))
    )
    (net (code "110") (name "unconnected-(IC4-QD-Pad3)") (class "Default")
      (node (ref "IC4") (pin "3") (pinfunction "QD_3") (pintype "tri_state"))
    )
    (net (code "111") (name "unconnected-(IC4-QG-Pad6)") (class "Default")
      (node (ref "IC4") (pin "6") (pinfunction "QG_6") (pintype "tri_state"))
    )
    (net (code "112") (name "unconnected-(IC4-SCK-Pad11)") (class "Default")
      (node (ref "IC4") (pin "11") (pinfunction "SCK_11") (pintype "input"))
    )
    (net (code "113") (name "unconnected-(IC4-SER-Pad14)") (class "Default")
      (node (ref "IC4") (pin "14") (pinfunction "SER_14") (pintype "input"))
    )
    (net (code "114") (name "unconnected-(IC5-QD-Pad3)") (class "Default")
      (node (ref "IC5") (pin "3") (pinfunction "QD_3") (pintype "tri_state"))
    )
    (net (code "115") (name "unconnected-(IC5-QG-Pad6)") (class "Default")
      (node (ref "IC5") (pin "6") (pinfunction "QG_6") (pintype "tri_state"))
    )
    (net (code "116") (name "unconnected-(IC5-SCK-Pad11)") (class "Default")
      (node (ref "IC5") (pin "11") (pinfunction "SCK_11") (pintype "input"))
    )
    (net (code "117") (name "unconnected-(IC5-SER-Pad14)") (class "Default")
      (node (ref "IC5") (pin "14") (pinfunction "SER_14") (pintype "input"))
    )
    (net (code "118") (name "unconnected-(IC6-QD-Pad3)") (class "Default")
      (node (ref "IC6") (pin "3") (pinfunction "QD_3") (pintype "tri_state"))
    )
    (net (code "119") (name "unconnected-(IC6-QG-Pad6)") (class "Default")
      (node (ref "IC6") (pin "6") (pinfunction "QG_6") (pintype "tri_state"))
    )
    (net (code "120") (name "unconnected-(IC6-SCK-Pad11)") (class "Default")
      (node (ref "IC6") (pin "11") (pinfunction "SCK_11") (pintype "input"))
    )
    (net (code "121") (name "unconnected-(IC6-SER-Pad14)") (class "Default")
      (node (ref "IC6") (pin "14") (pinfunction "SER_14") (pintype "input"))
    )
    (net (code "122") (name "unconnected-(IC7-QD-Pad3)") (class "Default")
      (node (ref "IC7") (pin "3") (pinfunction "QD_3") (pintype "tri_state"))
    )
    (net (code "123") (name "unconnected-(IC7-QG-Pad6)") (class "Default")
      (node (ref "IC7") (pin "6") (pinfunction "QG_6") (pintype "tri_state"))
    )
    (net (code "124") (name "unconnected-(IC7-SCK-Pad11)") (class "Default")
      (node (ref "IC7") (pin "11") (pinfunction "SCK_11") (pintype "input"))
    )
    (net (code "125") (name "unconnected-(IC7-SER-Pad14)") (class "Default")
      (node (ref "IC7") (pin "14") (pinfunction "SER_14") (pintype "input"))
    )
    (net (code "126") (name "unconnected-(IC8D-I0-Pad9)") (class "Default")
      (node (ref "IC8") (pin "9") (pinfunction "I0_9") (pintype "input"))
    )
    (net (code "127") (name "unconnected-(IC8D-I1-Pad8)") (class "Default")
      (node (ref "IC8") (pin "8") (pinfunction "I1_8") (pintype "input"))
    )
    (net (code "128") (name "unconnected-(IC8D-O-Pad7)") (class "Default")
      (node (ref "IC8") (pin "7") (pinfunction "O_7") (pintype "output"))
    )
    (net (code "129") (name "unconnected-(IC10A-A-Pad15)") (class "Default")
      (node (ref "IC10") (pin "15") (pinfunction "A_15") (pintype "input"))
    )
    (net (code "130") (name "unconnected-(IC10A-B-Pad1)") (class "Default")
      (node (ref "IC10") (pin "1") (pinfunction "B_1") (pintype "input"))
    )
    (net (code "131") (name "unconnected-(IC10A-BORROW-Pad13)") (class "Default")
      (node (ref "IC10") (pin "13") (pinfunction "BORROW_13") (pintype "output"))
    )
    (net (code "132") (name "unconnected-(IC10A-C-Pad10)") (class "Default")
      (node (ref "IC10") (pin "10") (pinfunction "C_10") (pintype "input"))
    )
    (net (code "133") (name "unconnected-(IC10A-CARRY-Pad12)") (class "Default")
      (node (ref "IC10") (pin "12") (pinfunction "CARRY_12") (pintype "output"))
    )
    (net (code "134") (name "unconnected-(IC10A-D-Pad9)") (class "Default")
      (node (ref "IC10") (pin "9") (pinfunction "D_9") (pintype "input"))
    )
    (net (code "135") (name "unconnected-(SPI0-Pad1)") (class "Default")
      (node (ref "SPI0") (pin "1") (pinfunction "1_1") (pintype "passive"))
    )
    (net (code "136") (name "unconnected-(SPI0-Pad2)") (class "Default")
      (node (ref "SPI0") (pin "2") (pinfunction "2_2") (pintype "passive"))
    )
    (net (code "137") (name "unconnected-(SPI0-Pad3)") (class "Default")
      (node (ref "SPI0") (pin "3") (pinfunction "3_3") (pintype "passive"))
    )
    (net (code "138") (name "unconnected-(SPI0-Pad4)") (class "Default")
      (node (ref "SPI0") (pin "4") (pinfunction "4_4") (pintype "passive"))
    )
    (net (code "139") (name "unconnected-(SPI0-Pad5)") (class "Default")
      (node (ref "SPI0") (pin "5") (pinfunction "5_5") (pintype "passive"))
    )
    (net (code "140") (name "unconnected-(SPI0-Pad6)") (class "Default")
      (node (ref "SPI0") (pin "6") (pinfunction "6_6") (pintype "passive"))
    )
    (net (code "141") (name "unconnected-(SPI1-Pad1)") (class "Default")
      (node (ref "SPI1") (pin "1") (pinfunction "1_1") (pintype "passive"))
    )
    (net (code "142") (name "unconnected-(SPI1-Pad2)") (class "Default")
      (node (ref "SPI1") (pin "2") (pinfunction "2_2") (pintype "passive"))
    )
    (net (code "143") (name "unconnected-(SPI1-Pad3)") (class "Default")
      (node (ref "SPI1") (pin "3") (pinfunction "3_3") (pintype "passive"))
    )
    (net (code "144") (name "unconnected-(SPI1-Pad4)") (class "Default")
      (node (ref "SPI1") (pin "4") (pinfunction "4_4") (pintype "passive"))
    )
    (net (code "145") (name "unconnected-(SPI1-Pad5)") (class "Default")
      (node (ref "SPI1") (pin "5") (pinfunction "5_5") (pintype "passive"))
    )
    (net (code "146") (name "unconnected-(SPI1-Pad6)") (class "Default")
      (node (ref "SPI1") (pin "6") (pinfunction "6_6") (pintype "passive"))
    )
    (net (code "147") (name "unconnected-(U1-NC-Pad63)") (class "Default")
      (node (ref "U1") (pin "63") (pinfunction "NC_63") (pintype "passive"))
    )
    (net (code "148") (name "unconnected-(U1-NC_2-Pad50)") (class "Default")
      (node (ref "U1") (pin "50") (pinfunction "NC_2_50") (pintype "passive"))
    )
    (net (code "149") (name "unconnected-(U1-NC_3-Pad51)") (class "Default")
      (node (ref "U1") (pin "51") (pinfunction "NC_3_51") (pintype "passive"))
    )
    (net (code "150") (name "unconnected-(U1-NC_4-Pad36)") (class "Default")
      (node (ref "U1") (pin "36") (pinfunction "NC_4_36") (pintype "passive"))
    )
    (net (code "151") (name "unconnected-(U1-NC_5-Pad62)") (class "Default")
      (node (ref "U1") (pin "62") (pinfunction "NC_5_62") (pintype "passive"))
    )
    (net (code "152") (name "unconnected-(U1-NC_6-Pad37)") (class "Default")
      (node (ref "U1") (pin "37") (pinfunction "NC_6_37") (pintype "passive"))
    )
    (net (code "153") (name "unconnected-(U1-REFCM-Pad19)") (class "Default")
      (node (ref "U1") (pin "19") (pinfunction "REFCM_19") (pintype "passive"))
    )
    (net (code "154") (name "unconnected-(U1-SOGIN0-Pad8)") (class "Default")
      (node (ref "U1") (pin "8") (pinfunction "SOGIN0_8") (pintype "passive"))
    )
    (net (code "155") (name "unconnected-(U1-SOGIN1-Pad12)") (class "Default")
      (node (ref "U1") (pin "12") (pinfunction "SOGIN1_12") (pintype "passive"))
    )
    (net (code "156") (name "unconnected-(U1-SOGOUT-Pad24)") (class "Default")
      (node (ref "U1") (pin "24") (pinfunction "SOGOUT_24") (pintype "passive"))
    )
    (net (code "157") (name "unconnected-(UART-Pad1)") (class "Default")
      (node (ref "UART") (pin "1") (pinfunction "1_1") (pintype "passive"))
    )
    (net (code "158") (name "unconnected-(UART-Pad2)") (class "Default")
      (node (ref "UART") (pin "2") (pinfunction "2_2") (pintype "passive"))
    )
    (net (code "159") (name "unconnected-(UART-Pad3)") (class "Default")
      (node (ref "UART") (pin "3") (pinfunction "3_3") (pintype "passive"))
    )
    (net (code "160") (name "unconnected-(UART-Pad4)") (class "Default")
      (node (ref "UART") (pin "4") (pinfunction "4_4") (pintype "passive"))
    )
  )
)
